# Schematic.net
KiCad netlist of a schematic drawn in Altium Designer
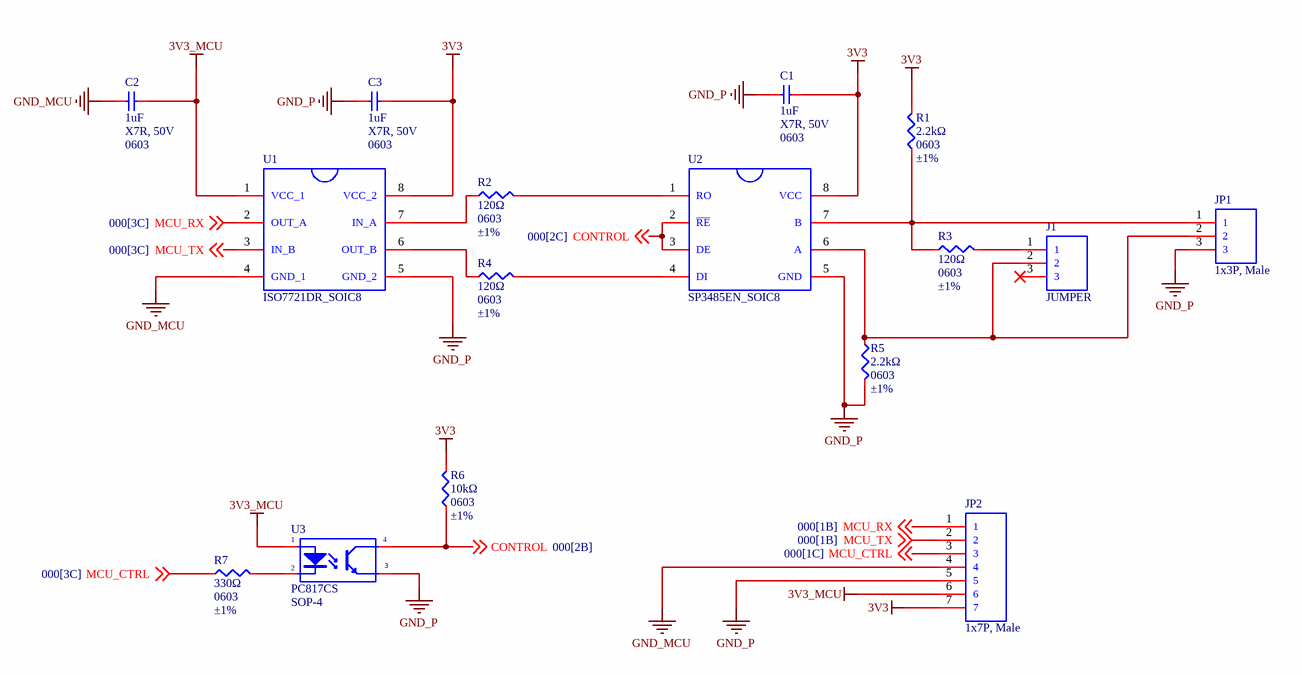
[diagram p0: Schematic.SchDoc]

(export (version "E")
  (design (tool "Eeschema 10.0.6"))
  (components
    (comp (ref "C1")
      (value "1uF")
      (footprint "C0603")
      (description "50V 1uF X7R ±10% 0603 Multilayer Ceramic Capacitors MLCC - SMD/SMT ROHS")
      (fields
        (field (name "MANUFACTURER") "YAGEO")
        (field (name "MFR. PART") "CC0603KRX7R9BB105")
        (field (name "TEMPERATURE COEFFICIENT") "X7R, 50V")
        (field (name "PACKAGE") "0603")
      )
      (libsource (lib "Capacitor") (part "C0603_MLCC_1uF_X7R_50V"))
    )
    (comp (ref "C2")
      (value "1uF")
      (footprint "C0603")
      (description "50V 1uF X7R ±10% 0603 Multilayer Ceramic Capacitors MLCC - SMD/SMT ROHS")
      (fields
        (field (name "MANUFACTURER") "YAGEO")
        (field (name "MFR. PART") "CC0603KRX7R9BB105")
        (field (name "TEMPERATURE COEFFICIENT") "X7R, 50V")
        (field (name "PACKAGE") "0603")
      )
      (libsource (lib "Capacitor") (part "C0603_MLCC_1uF_X7R_50V"))
    )
    (comp (ref "C3")
      (value "1uF")
      (footprint "C0603")
      (description "50V 1uF X7R ±10% 0603 Multilayer Ceramic Capacitors MLCC - SMD/SMT ROHS")
      (fields
        (field (name "MANUFACTURER") "YAGEO")
        (field (name "MFR. PART") "CC0603KRX7R9BB105")
        (field (name "TEMPERATURE COEFFICIENT") "X7R, 50V")
        (field (name "PACKAGE") "0603")
      )
      (libsource (lib "Capacitor") (part "C0603_MLCC_1uF_X7R_50V"))
    )
    (comp (ref "J1")
      (value "JUMPER")
      (footprint "JUMPER_SHUNT_3P")
      (fields
        (field (name "MANUFACTURER") "XFCN")
        (field (name "MFR. PART") "PZ254V-11-03P")
        (field (name "LCSC PART") "C2937625")
      )
      (libsource (lib "JUMP") (part "JUMPER_SHUNT_3P"))
    )
    (comp (ref "JP1")
      (value "1x3P, Male")
      (footprint "JST S3B-XH-A(LF)(SN)")
      (fields
        (field (name "MANUFACTURER") "JST")
        (field (name "MFR. PART") "S3B-XH-A(LF)(SN)")
        (field (name "LCSC PART") "C157928")
      )
      (libsource (lib "CONNECTER") (part "JST S3B-XH-A(LF)(SN)"))
    )
    (comp (ref "JP2")
      (value "1x7P, Male")
      (footprint "S7B-XH-A(LF)(SN)")
      (fields
        (field (name "MANUFACTURER") "JST")
        (field (name "MFR. PART") "S7B-XH-A(LF)(SN)")
        (field (name "LCSC PART") "C157916")
      )
      (libsource (lib "CONNECTER") (part "JST S7B-XH-A(LF)(SN)"))
    )
    (comp (ref "R1")
      (value "2.2kΩ")
      (footprint "R0603")
      (description "100mW 2.2kΩ 75V ±100ppm/℃ Thick Film Resistor ±1% 0603 Chip Resistor - Surface Mount ROHS")
      (fields
        (field (name "MANUFACTURER") "YAGEO")
        (field (name "MFR. PART") "RC0603FR-072K2L")
        (field (name "PACKAGE") "0603")
        (field (name "TOLERANCE") "±1%")
      )
      (libsource (lib "Resistor") (part "R0603_2.2KΩ_±1%"))
    )
    (comp (ref "R2")
      (value "120Ω")
      (footprint "R0603")
      (description "100mW 120Ω 75V ±100ppm/℃ Thick Film Resistor ±1% 0603 Chip Resistor - Surface Mount ROHS")
      (fields
        (field (name "MANUFACTURER") "YAGEO")
        (field (name "MFR. PART") "RC0603FR-07120RL")
        (field (name "PACKAGE") "0603")
        (field (name "TOLERANCE") "±1%")
      )
      (libsource (lib "Resistor") (part "R0603_120Ω_±1%"))
    )
    (comp (ref "R3")
      (value "120Ω")
      (footprint "R0603")
      (description "100mW 120Ω 75V ±100ppm/℃ Thick Film Resistor ±1% 0603 Chip Resistor - Surface Mount ROHS")
      (fields
        (field (name "MANUFACTURER") "YAGEO")
        (field (name "MFR. PART") "RC0603FR-07120RL")
        (field (name "PACKAGE") "0603")
        (field (name "TOLERANCE") "±1%")
      )
      (libsource (lib "Resistor") (part "R0603_120Ω_±1%"))
    )
    (comp (ref "R4")
      (value "120Ω")
      (footprint "R0603")
      (description "100mW 120Ω 75V ±100ppm/℃ Thick Film Resistor ±1% 0603 Chip Resistor - Surface Mount ROHS")
      (fields
        (field (name "MANUFACTURER") "YAGEO")
        (field (name "MFR. PART") "RC0603FR-07120RL")
        (field (name "PACKAGE") "0603")
        (field (name "TOLERANCE") "±1%")
      )
      (libsource (lib "Resistor") (part "R0603_120Ω_±1%"))
    )
    (comp (ref "R5")
      (value "2.2kΩ")
      (footprint "R0603")
      (description "100mW 2.2kΩ 75V ±100ppm/℃ Thick Film Resistor ±1% 0603 Chip Resistor - Surface Mount ROHS")
      (fields
        (field (name "MANUFACTURER") "YAGEO")
        (field (name "MFR. PART") "RC0603FR-072K2L")
        (field (name "PACKAGE") "0603")
        (field (name "TOLERANCE") "±1%")
      )
      (libsource (lib "Resistor") (part "R0603_2.2KΩ_±1%"))
    )
    (comp (ref "R6")
      (value "10kΩ")
      (footprint "R0603")
      (description "100mW Thick Film Resistor 75V ±100ppm/℃ ±1% 10kΩ 0603 Chip Resistor - Surface Mount ROHS")
      (fields
        (field (name "MANUFACTURER") "YAGEO")
        (field (name "MFR. PART") "RC0603FR-0710KL")
        (field (name "PACKAGE") "0603")
        (field (name "TOLERANCE") "±1%")
      )
      (libsource (lib "Resistor") (part "R0603_10kΩ_±1%"))
    )
    (comp (ref "R7")
      (value "330Ω")
      (footprint "R0603")
      (description "100mW Thick Film Resistor 75V ±100ppm/℃ ±1% 330Ω 0603 Chip Resistor - Surface Mount ROHS")
      (fields
        (field (name "MANUFACTURER") "YAGEO")
        (field (name "MFR. PART") "RC0603FR-07330RL")
        (field (name "PACKAGE") "0603")
        (field (name "TOLERANCE") "±1%")
      )
      (libsource (lib "Resistor") (part "R0603_330Ω_±1%"))
    )
    (comp (ref "U1")
      (value "ISO7721DR_SOIC8")
      (footprint "SOIC-8")
      (description "100Mbps SOIC-8 Digital Isolators ROHS")
      (fields (field (name "MANUFACTURER") "TI") (field (name "MFR. PART") "ISO7721DR"))
      (libsource (lib "IC") (part "ISO7721DR_SOIC8"))
    )
    (comp (ref "U2")
      (value "SP3485EN_SOIC8")
      (footprint "SOIC-8")
      (description "Transceiver 32 Half-Duplex 3.3V SOIC-8 Drivers, Receivers, Transceivers ROHS")
      (fields (field (name "MANUFACTURER") "MaxLinear") (field (name "MFR. PART") "SP3485EN-L/TR"))
      (libsource (lib "IC") (part "SP3485EN-L/TR_SOIC8"))
    )
    (comp (ref "U3")
      (value "PC817CS")
      (footprint "SOP-4")
      (description "50mA 200mV@1mA,20mA 80V 6V 1.2V DC SOP-4 Transistor, Photovoltaic Output Optoisolators ROHS")
      (fields
        (field (name "MANUFACTURER") "AOTE")
        (field (name "LCSC PART") "C20612591")
        (field (name "PACKAGE") "SOP-4")
      )
      (libsource (lib "OPTO") (part "PC817CS"))
    )
  )
  (nets
    (net (code "1") (name "3V3") (class "Default")
      (node (ref "C1") (pin "2") (pinfunction "2_2") (pintype "passive"))
      (node (ref "C3") (pin "2") (pinfunction "2_2") (pintype "passive"))
      (node (ref "JP2") (pin "7") (pinfunction "7_7") (pintype "passive"))
      (node (ref "R1") (pin "2") (pinfunction "2_2") (pintype "passive"))
      (node (ref "R6") (pin "2") (pinfunction "2_2") (pintype "passive"))
      (node (ref "U1") (pin "8") (pinfunction "VCC_2_8") (pintype "passive"))
      (node (ref "U2") (pin "8") (pinfunction "VCC_8") (pintype "passive"))
    )
    (net (code "2") (name "3V3_MCU") (class "Default")
      (node (ref "C2") (pin "2") (pinfunction "2_2") (pintype "passive"))
      (node (ref "JP2") (pin "6") (pinfunction "6_6") (pintype "passive"))
      (node (ref "U1") (pin "1") (pinfunction "VCC_1_1") (pintype "passive"))
      (node (ref "U3") (pin "1") (pinfunction "A_1") (pintype "passive"))
    )
    (net (code "3") (name "CONTROL") (class "Default")
      (node (ref "R6") (pin "1") (pinfunction "1_1") (pintype "passive"))
      (node (ref "U2") (pin "2") (pinfunction "~{RE}_2") (pintype "passive"))
      (node (ref "U2") (pin "3") (pinfunction "DE_3") (pintype "passive"))
      (node (ref "U3") (pin "4") (pinfunction "C_4") (pintype "passive"))
    )
    (net (code "4") (name "GND_MCU") (class "Default")
      (node (ref "C2") (pin "1") (pinfunction "1_1") (pintype "passive"))
      (node (ref "JP2") (pin "4") (pinfunction "4_4") (pintype "passive"))
      (node (ref "U1") (pin "4") (pinfunction "GND_1_4") (pintype "passive"))
    )
    (net (code "5") (name "GND_P") (class "Default")
      (node (ref "C1") (pin "1") (pinfunction "1_1") (pintype "passive"))
      (node (ref "C3") (pin "1") (pinfunction "1_1") (pintype "passive"))
      (node (ref "JP1") (pin "3") (pinfunction "3_3") (pintype "passive"))
      (node (ref "JP2") (pin "5") (pinfunction "5_5") (pintype "passive"))
      (node (ref "R5") (pin "2") (pinfunction "2_2") (pintype "passive"))
      (node (ref "U1") (pin "5") (pinfunction "GND_2_5") (pintype "passive"))
      (node (ref "U2") (pin "5") (pinfunction "GND_5") (pintype "passive"))
      (node (ref "U3") (pin "3") (pinfunction "E_3") (pintype "passive"))
    )
    (net (code "6") (name "MCU_CTRL") (class "Default")
      (node (ref "JP2") (pin "3") (pinfunction "3_3") (pintype "passive"))
      (node (ref "R7") (pin "1") (pinfunction "1_1") (pintype "passive"))
    )
    (net (code "7") (name "MCU_RX") (class "Default")
      (node (ref "JP2") (pin "1") (pinfunction "1_1") (pintype "passive"))
      (node (ref "U1") (pin "2") (pinfunction "OUT_A_2") (pintype "passive"))
    )
    (net (code "8") (name "MCU_TX") (class "Default")
      (node (ref "JP2") (pin "2") (pinfunction "2_2") (pintype "passive"))
      (node (ref "U1") (pin "3") (pinfunction "IN_B_3") (pintype "passive"))
    )
    (net (code "9") (name "Net-(J1-Pad1)") (class "Default")
      (node (ref "J1") (pin "1") (pinfunction "1_1") (pintype "passive"))
      (node (ref "R3") (pin "2") (pinfunction "2_2") (pintype "passive"))
    )
    (net (code "10") (name "Net-(U1-IN_A)") (class "Default")
      (node (ref "R2") (pin "1") (pinfunction "1_1") (pintype "passive"))
      (node (ref "U1") (pin "7") (pinfunction "IN_A_7") (pintype "passive"))
    )
    (net (code "11") (name "Net-(U1-OUT_B)") (class "Default")
      (node (ref "R4") (pin "1") (pinfunction "1_1") (pintype "passive"))
      (node (ref "U1") (pin "6") (pinfunction "OUT_B_6") (pintype "passive"))
    )
    (net (code "12") (name "Net-(U2-A)") (class "Default")
      (node (ref "J1") (pin "2") (pinfunction "2_2") (pintype "passive"))
      (node (ref "JP1") (pin "2") (pinfunction "2_2") (pintype "passive"))
      (node (ref "R5") (pin "1") (pinfunction "1_1") (pintype "passive"))
      (node (ref "U2") (pin "6") (pinfunction "A_6") (pintype "passive"))
    )
    (net (code "13") (name "Net-(U2-B)") (class "Default")
      (node (ref "JP1") (pin "1") (pinfunction "1_1") (pintype "passive"))
      (node (ref "R1") (pin "1") (pinfunction "1_1") (pintype "passive"))
      (node (ref "R3") (pin "1") (pinfunction "1_1") (pintype "passive"))
      (node (ref "U2") (pin "7") (pinfunction "B_7") (pintype "passive"))
    )
    (net (code "14") (name "Net-(U2-DI)") (class "Default")
      (node (ref "R4") (pin "2") (pinfunction "2_2") (pintype "passive"))
      (node (ref "U2") (pin "4") (pinfunction "DI_4") (pintype "passive"))
    )
    (net (code "15") (name "Net-(U2-RO)") (class "Default")
      (node (ref "R2") (pin "2") (pinfunction "2_2") (pintype "passive"))
      (node (ref "U2") (pin "1") (pinfunction "RO_1") (pintype "passive"))
    )
    (net (code "16") (name "Net-(U3-K)") (class "Default")
      (node (ref "R7") (pin "2") (pinfunction "2_2") (pintype "passive"))
      (node (ref "U3") (pin "2") (pinfunction "K_2") (pintype "passive"))
    )
    (net (code "17") (name "unconnected-(J1-Pad3)") (class "Default")
      (node (ref "J1") (pin "3") (pinfunction "3_3") (pintype "passive+no_connect"))
    )
  )
)
